# shifty.net
KiCad netlist of a schematic drawn in EAGLE
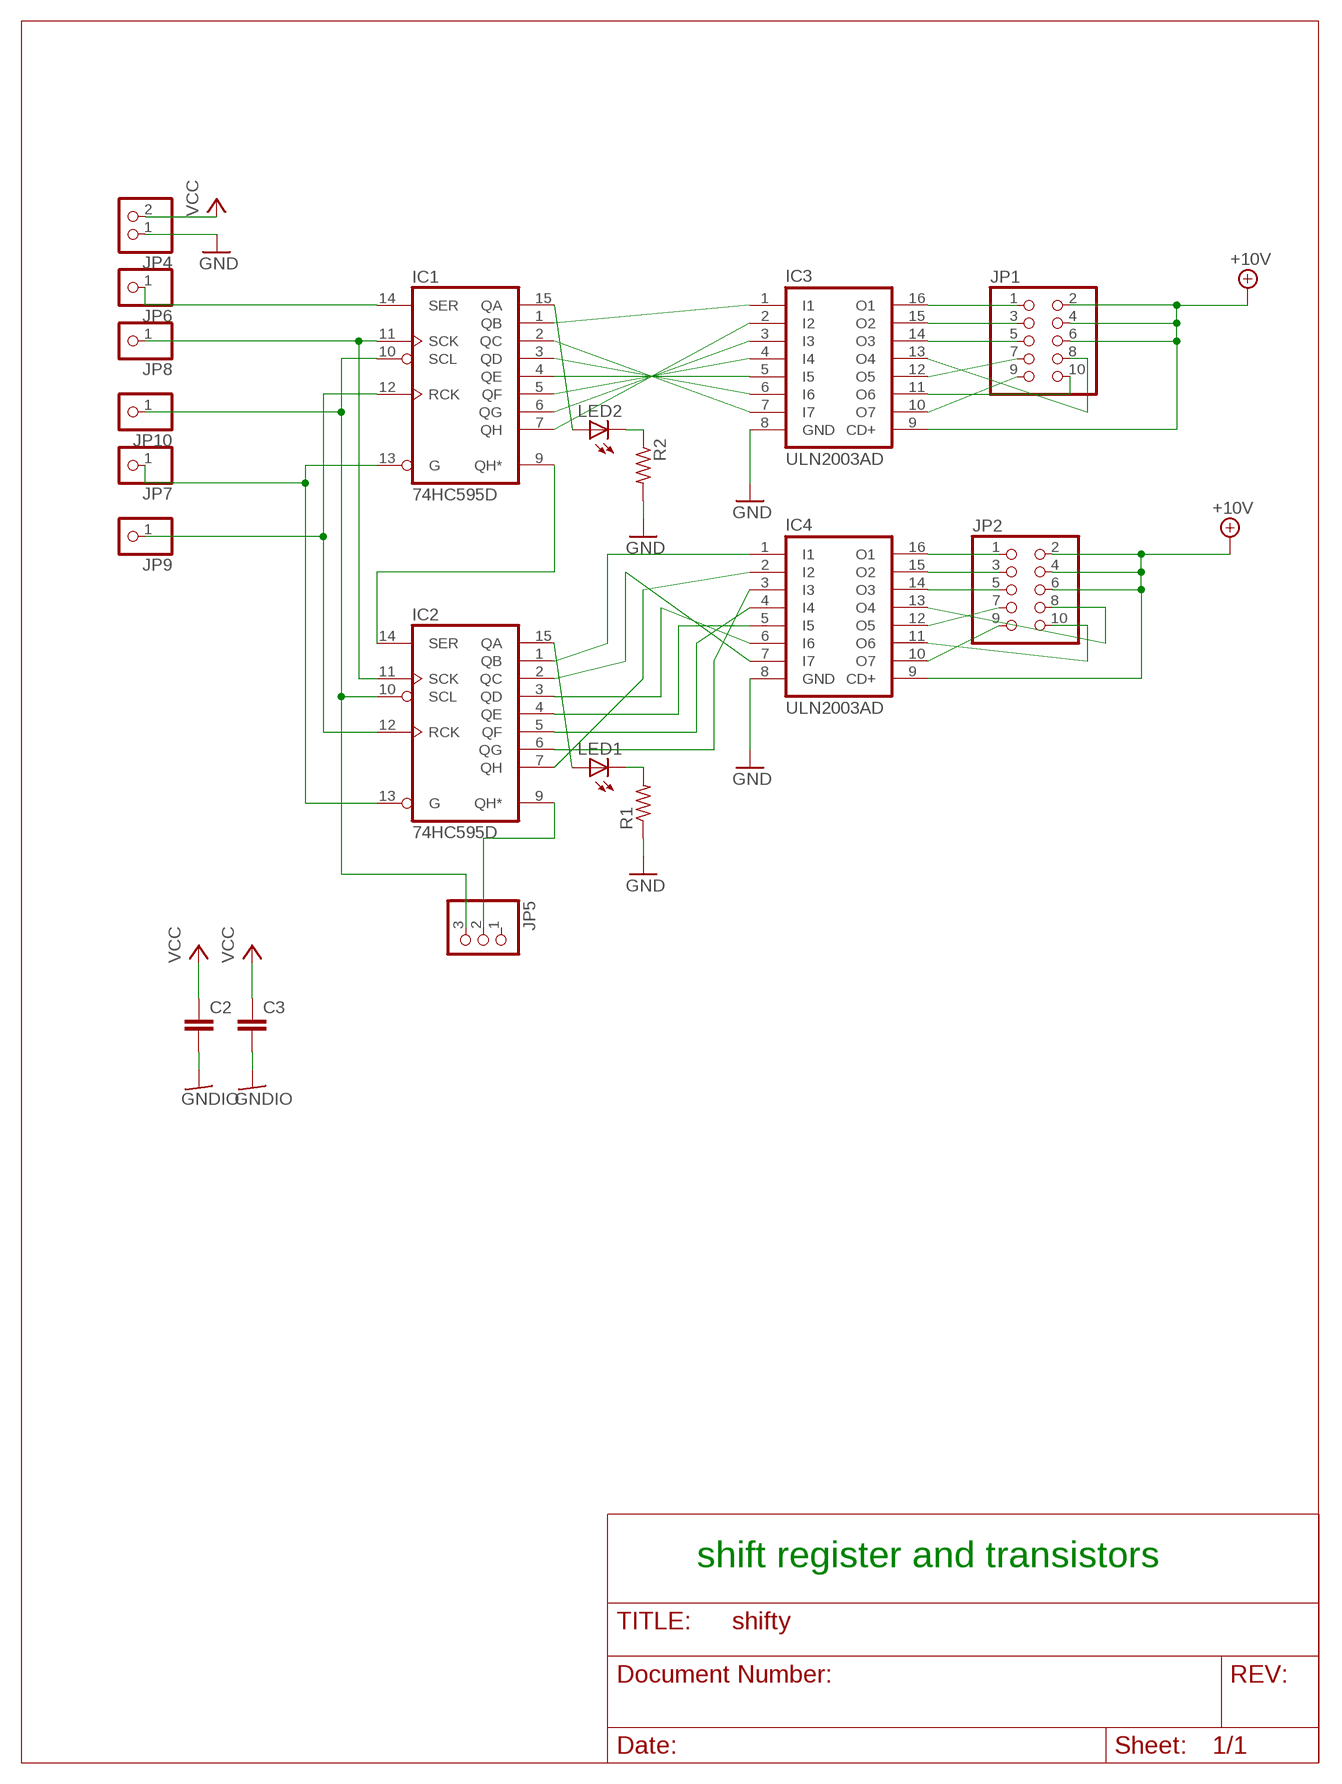
[diagram p0: schematic, sheet 1]

(export (version "E")
  (design (tool "Eeschema 10.0.6"))
  (components
    (comp (ref "C2")
      (value "C-EUC0805")
      (footprint "eagle-import:C0805")
      (libsource (lib "eagle-import") (part "C-EUC0805"))
    )
    (comp (ref "C3")
      (value "C-EUC0805")
      (footprint "eagle-import:C0805")
      (libsource (lib "eagle-import") (part "C-EUC0805"))
    )
    (comp (ref "IC1")
      (value "74HC595D")
      (footprint "eagle-import:SO16")
      (libsource (lib "eagle-import") (part "74595DHC"))
    )
    (comp (ref "IC2")
      (value "74HC595D")
      (footprint "eagle-import:SO16")
      (libsource (lib "eagle-import") (part "74595DHC"))
    )
    (comp (ref "IC3")
      (value "ULN2003AD")
      (footprint "eagle-import:SO16")
      (libsource (lib "eagle-import") (part "ULN2003AD"))
    )
    (comp (ref "IC4")
      (value "ULN2003AD")
      (footprint "eagle-import:SO16")
      (libsource (lib "eagle-import") (part "ULN2003AD"))
    )
    (comp (ref "JP1")
      (value "PINHD-2X5")
      (footprint "eagle-import:2X05")
      (libsource (lib "eagle-import") (part "PINHD-2X5"))
    )
    (comp (ref "JP2")
      (value "PINHD-2X5")
      (footprint "eagle-import:2X05")
      (libsource (lib "eagle-import") (part "PINHD-2X5"))
    )
    (comp (ref "JP4")
      (value "PINHD-1X2")
      (footprint "eagle-import:1X02")
      (libsource (lib "eagle-import") (part "PINHD-1X2"))
    )
    (comp (ref "JP5")
      (value "PINHD-1X3")
      (footprint "eagle-import:1X03")
      (libsource (lib "eagle-import") (part "PINHD-1X3"))
    )
    (comp (ref "JP6")
      (value "PINHD-1X1")
      (footprint "eagle-import:1X01")
      (libsource (lib "eagle-import") (part "PINHD-1X1"))
    )
    (comp (ref "JP7")
      (value "PINHD-1X1")
      (footprint "eagle-import:1X01")
      (libsource (lib "eagle-import") (part "PINHD-1X1"))
    )
    (comp (ref "JP8")
      (value "PINHD-1X1")
      (footprint "eagle-import:1X01")
      (libsource (lib "eagle-import") (part "PINHD-1X1"))
    )
    (comp (ref "JP9")
      (value "PINHD-1X1")
      (footprint "eagle-import:1X01")
      (libsource (lib "eagle-import") (part "PINHD-1X1"))
    )
    (comp (ref "JP10")
      (value "PINHD-1X1")
      (footprint "eagle-import:1X01")
      (libsource (lib "eagle-import") (part "PINHD-1X1"))
    )
    (comp (ref "LED1")
      (value "LEDCHIP-LED0603")
      (footprint "eagle-import:CHIP-LED0603")
      (libsource (lib "eagle-import") (part "LEDCHIP-LED0603"))
    )
    (comp (ref "LED2")
      (value "LEDCHIP-LED0603")
      (footprint "eagle-import:CHIP-LED0603")
      (libsource (lib "eagle-import") (part "LEDCHIP-LED0603"))
    )
    (comp (ref "R1")
      (value "R-US_R0603")
      (footprint "eagle-import:R0603")
      (libsource (lib "eagle-import") (part "R-US_R0603"))
    )
    (comp (ref "R2")
      (value "R-US_R0603")
      (footprint "eagle-import:R0603")
      (libsource (lib "eagle-import") (part "R-US_R0603"))
    )
  )
  (nets
    (net (code "1") (name "+10V") (class "Default")
      (node (ref "IC3") (pin "9") (pinfunction "CD+_9") (pintype "passive"))
      (node (ref "IC4") (pin "9") (pinfunction "CD+_9") (pintype "passive"))
      (node (ref "JP1") (pin "2") (pinfunction "2_2") (pintype "passive"))
      (node (ref "JP1") (pin "4") (pinfunction "4_4") (pintype "passive"))
      (node (ref "JP1") (pin "6") (pinfunction "6_6") (pintype "passive"))
      (node (ref "JP2") (pin "2") (pinfunction "2_2") (pintype "passive"))
      (node (ref "JP2") (pin "4") (pinfunction "4_4") (pintype "passive"))
      (node (ref "JP2") (pin "6") (pinfunction "6_6") (pintype "passive"))
    )
    (net (code "2") (name "GND") (class "Default")
      (node (ref "IC3") (pin "8") (pinfunction "GND_8") (pintype "power_in"))
      (node (ref "IC4") (pin "8") (pinfunction "GND_8") (pintype "power_in"))
      (node (ref "JP4") (pin "1") (pinfunction "1_1") (pintype "passive"))
      (node (ref "R1") (pin "1") (pinfunction "1_1") (pintype "passive"))
      (node (ref "R2") (pin "2") (pinfunction "2_2") (pintype "passive"))
    )
    (net (code "3") (name "GNDIO") (class "Default")
      (node (ref "C2") (pin "2") (pinfunction "2_2") (pintype "passive"))
      (node (ref "C3") (pin "2") (pinfunction "2_2") (pintype "passive"))
    )
    (net (code "4") (name "Net-(IC1A-G)") (class "Default")
      (node (ref "IC1") (pin "13") (pinfunction "G_13") (pintype "input"))
      (node (ref "IC2") (pin "13") (pinfunction "G_13") (pintype "input"))
      (node (ref "JP7") (pin "1") (pinfunction "1_1") (pintype "passive"))
    )
    (net (code "5") (name "Net-(IC1A-QA)") (class "Default")
      (node (ref "IC1") (pin "15") (pinfunction "QA_15") (pintype "tri_state"))
      (node (ref "LED2") (pin "A") (pinfunction "A_A") (pintype "passive"))
    )
    (net (code "6") (name "Net-(IC1A-QB)") (class "Default")
      (node (ref "IC1") (pin "1") (pinfunction "QB_1") (pintype "tri_state"))
      (node (ref "IC3") (pin "1") (pinfunction "I1_1") (pintype "input"))
    )
    (net (code "7") (name "Net-(IC1A-QC)") (class "Default")
      (node (ref "IC1") (pin "2") (pinfunction "QC_2") (pintype "tri_state"))
      (node (ref "IC3") (pin "7") (pinfunction "I7_7") (pintype "input"))
    )
    (net (code "8") (name "Net-(IC1A-QD)") (class "Default")
      (node (ref "IC1") (pin "3") (pinfunction "QD_3") (pintype "tri_state"))
      (node (ref "IC3") (pin "6") (pinfunction "I6_6") (pintype "input"))
    )
    (net (code "9") (name "Net-(IC1A-QE)") (class "Default")
      (node (ref "IC1") (pin "4") (pinfunction "QE_4") (pintype "tri_state"))
      (node (ref "IC3") (pin "5") (pinfunction "I5_5") (pintype "input"))
    )
    (net (code "10") (name "Net-(IC1A-QF)") (class "Default")
      (node (ref "IC1") (pin "5") (pinfunction "QF_5") (pintype "tri_state"))
      (node (ref "IC3") (pin "4") (pinfunction "I4_4") (pintype "input"))
    )
    (net (code "11") (name "Net-(IC1A-QG)") (class "Default")
      (node (ref "IC1") (pin "6") (pinfunction "QG_6") (pintype "tri_state"))
      (node (ref "IC3") (pin "3") (pinfunction "I3_3") (pintype "input"))
    )
    (net (code "12") (name "Net-(IC1A-QH)") (class "Default")
      (node (ref "IC1") (pin "7") (pinfunction "QH_7") (pintype "tri_state"))
      (node (ref "IC3") (pin "2") (pinfunction "I2_2") (pintype "input"))
    )
    (net (code "13") (name "Net-(IC1A-QH*)") (class "Default")
      (node (ref "IC1") (pin "9") (pinfunction "QH*_9") (pintype "tri_state"))
      (node (ref "IC2") (pin "14") (pinfunction "SER_14") (pintype "input"))
    )
    (net (code "14") (name "Net-(IC1A-RCK)") (class "Default")
      (node (ref "IC1") (pin "12") (pinfunction "RCK_12") (pintype "input"))
      (node (ref "IC2") (pin "12") (pinfunction "RCK_12") (pintype "input"))
      (node (ref "JP9") (pin "1") (pinfunction "1_1") (pintype "passive"))
    )
    (net (code "15") (name "Net-(IC1A-SCK)") (class "Default")
      (node (ref "IC1") (pin "11") (pinfunction "SCK_11") (pintype "input"))
      (node (ref "IC2") (pin "11") (pinfunction "SCK_11") (pintype "input"))
      (node (ref "JP8") (pin "1") (pinfunction "1_1") (pintype "passive"))
    )
    (net (code "16") (name "Net-(IC1A-SCL)") (class "Default")
      (node (ref "IC1") (pin "10") (pinfunction "SCL_10") (pintype "input"))
      (node (ref "IC2") (pin "10") (pinfunction "SCL_10") (pintype "input"))
      (node (ref "JP10") (pin "1") (pinfunction "1_1") (pintype "passive"))
      (node (ref "JP5") (pin "3") (pinfunction "3_3") (pintype "passive"))
    )
    (net (code "17") (name "Net-(IC1A-SER)") (class "Default")
      (node (ref "IC1") (pin "14") (pinfunction "SER_14") (pintype "input"))
      (node (ref "JP6") (pin "1") (pinfunction "1_1") (pintype "passive"))
    )
    (net (code "18") (name "Net-(IC2A-QA)") (class "Default")
      (node (ref "IC2") (pin "15") (pinfunction "QA_15") (pintype "tri_state"))
      (node (ref "LED1") (pin "A") (pinfunction "A_A") (pintype "passive"))
    )
    (net (code "19") (name "Net-(IC2A-QB)") (class "Default")
      (node (ref "IC2") (pin "1") (pinfunction "QB_1") (pintype "tri_state"))
      (node (ref "IC4") (pin "1") (pinfunction "I1_1") (pintype "input"))
    )
    (net (code "20") (name "Net-(IC2A-QC)") (class "Default")
      (node (ref "IC2") (pin "2") (pinfunction "QC_2") (pintype "tri_state"))
      (node (ref "IC4") (pin "7") (pinfunction "I7_7") (pintype "input"))
    )
    (net (code "21") (name "Net-(IC2A-QD)") (class "Default")
      (node (ref "IC2") (pin "3") (pinfunction "QD_3") (pintype "tri_state"))
      (node (ref "IC4") (pin "6") (pinfunction "I6_6") (pintype "input"))
    )
    (net (code "22") (name "Net-(IC2A-QE)") (class "Default")
      (node (ref "IC2") (pin "4") (pinfunction "QE_4") (pintype "tri_state"))
      (node (ref "IC4") (pin "5") (pinfunction "I5_5") (pintype "input"))
    )
    (net (code "23") (name "Net-(IC2A-QF)") (class "Default")
      (node (ref "IC2") (pin "5") (pinfunction "QF_5") (pintype "tri_state"))
      (node (ref "IC4") (pin "4") (pinfunction "I4_4") (pintype "input"))
    )
    (net (code "24") (name "Net-(IC2A-QG)") (class "Default")
      (node (ref "IC2") (pin "6") (pinfunction "QG_6") (pintype "tri_state"))
      (node (ref "IC4") (pin "3") (pinfunction "I3_3") (pintype "input"))
    )
    (net (code "25") (name "Net-(IC2A-QH)") (class "Default")
      (node (ref "IC2") (pin "7") (pinfunction "QH_7") (pintype "tri_state"))
      (node (ref "IC4") (pin "2") (pinfunction "I2_2") (pintype "input"))
    )
    (net (code "26") (name "Net-(IC2A-QH*)") (class "Default")
      (node (ref "IC2") (pin "9") (pinfunction "QH*_9") (pintype "tri_state"))
      (node (ref "JP5") (pin "2") (pinfunction "2_2") (pintype "passive"))
    )
    (net (code "27") (name "Net-(IC3-O1)") (class "Default")
      (node (ref "IC3") (pin "16") (pinfunction "O1_16") (pintype "open_collector"))
      (node (ref "JP1") (pin "1") (pinfunction "1_1") (pintype "passive"))
    )
    (net (code "28") (name "Net-(IC3-O2)") (class "Default")
      (node (ref "IC3") (pin "15") (pinfunction "O2_15") (pintype "open_collector"))
      (node (ref "JP1") (pin "3") (pinfunction "3_3") (pintype "passive"))
    )
    (net (code "29") (name "Net-(IC3-O3)") (class "Default")
      (node (ref "IC3") (pin "14") (pinfunction "O3_14") (pintype "open_collector"))
      (node (ref "JP1") (pin "5") (pinfunction "5_5") (pintype "passive"))
    )
    (net (code "30") (name "Net-(IC3-O4)") (class "Default")
      (node (ref "IC3") (pin "13") (pinfunction "O4_13") (pintype "open_collector"))
      (node (ref "JP1") (pin "8") (pinfunction "8_8") (pintype "passive"))
    )
    (net (code "31") (name "Net-(IC3-O5)") (class "Default")
      (node (ref "IC3") (pin "12") (pinfunction "O5_12") (pintype "open_collector"))
      (node (ref "JP1") (pin "7") (pinfunction "7_7") (pintype "passive"))
    )
    (net (code "32") (name "Net-(IC3-O6)") (class "Default")
      (node (ref "IC3") (pin "11") (pinfunction "O6_11") (pintype "open_collector"))
      (node (ref "JP1") (pin "10") (pinfunction "10_10") (pintype "passive"))
    )
    (net (code "33") (name "Net-(IC3-O7)") (class "Default")
      (node (ref "IC3") (pin "10") (pinfunction "O7_10") (pintype "open_collector"))
      (node (ref "JP1") (pin "9") (pinfunction "9_9") (pintype "passive"))
    )
    (net (code "34") (name "Net-(IC4-O1)") (class "Default")
      (node (ref "IC4") (pin "16") (pinfunction "O1_16") (pintype "open_collector"))
      (node (ref "JP2") (pin "1") (pinfunction "1_1") (pintype "passive"))
    )
    (net (code "35") (name "Net-(IC4-O2)") (class "Default")
      (node (ref "IC4") (pin "15") (pinfunction "O2_15") (pintype "open_collector"))
      (node (ref "JP2") (pin "3") (pinfunction "3_3") (pintype "passive"))
    )
    (net (code "36") (name "Net-(IC4-O3)") (class "Default")
      (node (ref "IC4") (pin "14") (pinfunction "O3_14") (pintype "open_collector"))
      (node (ref "JP2") (pin "5") (pinfunction "5_5") (pintype "passive"))
    )
    (net (code "37") (name "Net-(IC4-O4)") (class "Default")
      (node (ref "IC4") (pin "13") (pinfunction "O4_13") (pintype "open_collector"))
      (node (ref "JP2") (pin "8") (pinfunction "8_8") (pintype "passive"))
    )
    (net (code "38") (name "Net-(IC4-O5)") (class "Default")
      (node (ref "IC4") (pin "12") (pinfunction "O5_12") (pintype "open_collector"))
      (node (ref "JP2") (pin "7") (pinfunction "7_7") (pintype "passive"))
    )
    (net (code "39") (name "Net-(IC4-O6)") (class "Default")
      (node (ref "IC4") (pin "11") (pinfunction "O6_11") (pintype "open_collector"))
      (node (ref "JP2") (pin "10") (pinfunction "10_10") (pintype "passive"))
    )
    (net (code "40") (name "Net-(IC4-O7)") (class "Default")
      (node (ref "IC4") (pin "10") (pinfunction "O7_10") (pintype "open_collector"))
      (node (ref "JP2") (pin "9") (pinfunction "9_9") (pintype "passive"))
    )
    (net (code "41") (name "Net-(LED1-PadC)") (class "Default")
      (node (ref "LED1") (pin "C") (pinfunction "C_C") (pintype "passive"))
      (node (ref "R1") (pin "2") (pinfunction "2_2") (pintype "passive"))
    )
    (net (code "42") (name "Net-(LED2-PadC)") (class "Default")
      (node (ref "LED2") (pin "C") (pinfunction "C_C") (pintype "passive"))
      (node (ref "R2") (pin "1") (pinfunction "1_1") (pintype "passive"))
    )
    (net (code "43") (name "VCC") (class "Default")
      (node (ref "C2") (pin "1") (pinfunction "1_1") (pintype "passive"))
      (node (ref "C3") (pin "1") (pinfunction "1_1") (pintype "passive"))
      (node (ref "JP4") (pin "2") (pinfunction "2_2") (pintype "passive"))
    )
    (net (code "44") (name "unconnected-(JP5-Pad1)") (class "Default")
      (node (ref "JP5") (pin "1") (pinfunction "1_1") (pintype "passive"))
    )
  )
)
